# panel7.net
KiCad netlist of a schematic drawn in Altium Designer
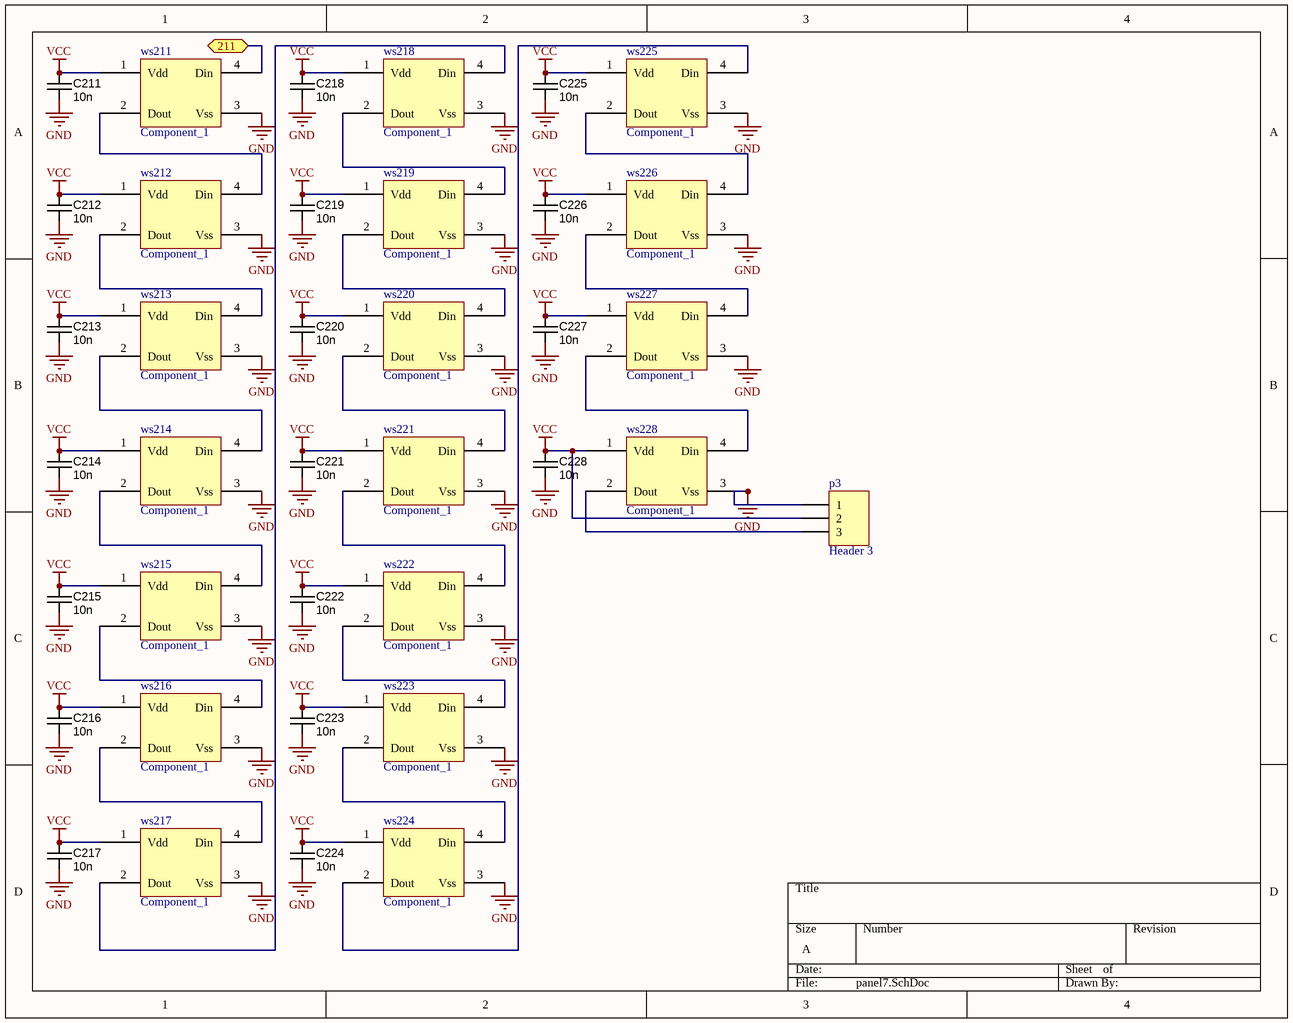
[diagram p0: panel7.SchDoc]

(export (version "E")
  (design (tool "Eeschema 10.0.6"))
  (components
    (comp (ref "C211")
      (value "10n")
      (footprint "CAPC1608X90N")
      (description "Capacitor SMD Cer 10nF 10% 100V X7R 0603")
      (fields
        (field (name "TOLERANCE") "±10%")
        (field (name "MANUFACTURER") "Murata Electronics North America")
      )
      (libsource (lib "PBL - Capacitors") (part "CAPC_10n_0603_X7R_100V_10%"))
    )
    (comp (ref "C212")
      (value "10n")
      (footprint "CAPC1608X90N")
      (description "Capacitor SMD Cer 10nF 10% 100V X7R 0603")
      (fields
        (field (name "TOLERANCE") "±10%")
        (field (name "MANUFACTURER") "Murata Electronics North America")
      )
      (libsource (lib "PBL - Capacitors") (part "CAPC_10n_0603_X7R_100V_10%"))
    )
    (comp (ref "C213")
      (value "10n")
      (footprint "CAPC1608X90N")
      (description "Capacitor SMD Cer 10nF 10% 100V X7R 0603")
      (fields
        (field (name "TOLERANCE") "±10%")
        (field (name "MANUFACTURER") "Murata Electronics North America")
      )
      (libsource (lib "PBL - Capacitors") (part "CAPC_10n_0603_X7R_100V_10%"))
    )
    (comp (ref "C214")
      (value "10n")
      (footprint "CAPC1608X90N")
      (description "Capacitor SMD Cer 10nF 10% 100V X7R 0603")
      (fields
        (field (name "TOLERANCE") "±10%")
        (field (name "MANUFACTURER") "Murata Electronics North America")
      )
      (libsource (lib "PBL - Capacitors") (part "CAPC_10n_0603_X7R_100V_10%"))
    )
    (comp (ref "C215")
      (value "10n")
      (footprint "CAPC1608X90N")
      (description "Capacitor SMD Cer 10nF 10% 100V X7R 0603")
      (fields
        (field (name "TOLERANCE") "±10%")
        (field (name "MANUFACTURER") "Murata Electronics North America")
      )
      (libsource (lib "PBL - Capacitors") (part "CAPC_10n_0603_X7R_100V_10%"))
    )
    (comp (ref "C216")
      (value "10n")
      (footprint "CAPC1608X90N")
      (description "Capacitor SMD Cer 10nF 10% 100V X7R 0603")
      (fields
        (field (name "TOLERANCE") "±10%")
        (field (name "MANUFACTURER") "Murata Electronics North America")
      )
      (libsource (lib "PBL - Capacitors") (part "CAPC_10n_0603_X7R_100V_10%"))
    )
    (comp (ref "C217")
      (value "10n")
      (footprint "CAPC1608X90N")
      (description "Capacitor SMD Cer 10nF 10% 100V X7R 0603")
      (fields
        (field (name "TOLERANCE") "±10%")
        (field (name "MANUFACTURER") "Murata Electronics North America")
      )
      (libsource (lib "PBL - Capacitors") (part "CAPC_10n_0603_X7R_100V_10%"))
    )
    (comp (ref "C218")
      (value "10n")
      (footprint "CAPC1608X90N")
      (description "Capacitor SMD Cer 10nF 10% 100V X7R 0603")
      (fields
        (field (name "TOLERANCE") "±10%")
        (field (name "MANUFACTURER") "Murata Electronics North America")
      )
      (libsource (lib "PBL - Capacitors") (part "CAPC_10n_0603_X7R_100V_10%"))
    )
    (comp (ref "C219")
      (value "10n")
      (footprint "CAPC1608X90N")
      (description "Capacitor SMD Cer 10nF 10% 100V X7R 0603")
      (fields
        (field (name "TOLERANCE") "±10%")
        (field (name "MANUFACTURER") "Murata Electronics North America")
      )
      (libsource (lib "PBL - Capacitors") (part "CAPC_10n_0603_X7R_100V_10%"))
    )
    (comp (ref "C220")
      (value "10n")
      (footprint "CAPC1608X90N")
      (description "Capacitor SMD Cer 10nF 10% 100V X7R 0603")
      (fields
        (field (name "TOLERANCE") "±10%")
        (field (name "MANUFACTURER") "Murata Electronics North America")
      )
      (libsource (lib "PBL - Capacitors") (part "CAPC_10n_0603_X7R_100V_10%"))
    )
    (comp (ref "C221")
      (value "10n")
      (footprint "CAPC1608X90N")
      (description "Capacitor SMD Cer 10nF 10% 100V X7R 0603")
      (fields
        (field (name "TOLERANCE") "±10%")
        (field (name "MANUFACTURER") "Murata Electronics North America")
      )
      (libsource (lib "PBL - Capacitors") (part "CAPC_10n_0603_X7R_100V_10%"))
    )
    (comp (ref "C222")
      (value "10n")
      (footprint "CAPC1608X90N")
      (description "Capacitor SMD Cer 10nF 10% 100V X7R 0603")
      (fields
        (field (name "TOLERANCE") "±10%")
        (field (name "MANUFACTURER") "Murata Electronics North America")
      )
      (libsource (lib "PBL - Capacitors") (part "CAPC_10n_0603_X7R_100V_10%"))
    )
    (comp (ref "C223")
      (value "10n")
      (footprint "CAPC1608X90N")
      (description "Capacitor SMD Cer 10nF 10% 100V X7R 0603")
      (fields
        (field (name "TOLERANCE") "±10%")
        (field (name "MANUFACTURER") "Murata Electronics North America")
      )
      (libsource (lib "PBL - Capacitors") (part "CAPC_10n_0603_X7R_100V_10%"))
    )
    (comp (ref "C224")
      (value "10n")
      (footprint "CAPC1608X90N")
      (description "Capacitor SMD Cer 10nF 10% 100V X7R 0603")
      (fields
        (field (name "TOLERANCE") "±10%")
        (field (name "MANUFACTURER") "Murata Electronics North America")
      )
      (libsource (lib "PBL - Capacitors") (part "CAPC_10n_0603_X7R_100V_10%"))
    )
    (comp (ref "C225")
      (value "10n")
      (footprint "CAPC1608X90N")
      (description "Capacitor SMD Cer 10nF 10% 100V X7R 0603")
      (fields
        (field (name "TOLERANCE") "±10%")
        (field (name "MANUFACTURER") "Murata Electronics North America")
      )
      (libsource (lib "PBL - Capacitors") (part "CAPC_10n_0603_X7R_100V_10%"))
    )
    (comp (ref "C226")
      (value "10n")
      (footprint "CAPC1608X90N")
      (description "Capacitor SMD Cer 10nF 10% 100V X7R 0603")
      (fields
        (field (name "TOLERANCE") "±10%")
        (field (name "MANUFACTURER") "Murata Electronics North America")
      )
      (libsource (lib "PBL - Capacitors") (part "CAPC_10n_0603_X7R_100V_10%"))
    )
    (comp (ref "C227")
      (value "10n")
      (footprint "CAPC1608X90N")
      (description "Capacitor SMD Cer 10nF 10% 100V X7R 0603")
      (fields
        (field (name "TOLERANCE") "±10%")
        (field (name "MANUFACTURER") "Murata Electronics North America")
      )
      (libsource (lib "PBL - Capacitors") (part "CAPC_10n_0603_X7R_100V_10%"))
    )
    (comp (ref "C228")
      (value "10n")
      (footprint "CAPC1608X90N")
      (description "Capacitor SMD Cer 10nF 10% 100V X7R 0603")
      (fields
        (field (name "TOLERANCE") "±10%")
        (field (name "MANUFACTURER") "Murata Electronics North America")
      )
      (libsource (lib "PBL - Capacitors") (part "CAPC_10n_0603_X7R_100V_10%"))
    )
    (comp (ref "p3")
      (value "Header 3")
      (footprint "HDR1X3")
      (description "Header, 3-Pin")
      (fields (field (name "PUBLISHER") "Altium Limited"))
      (libsource (lib "Miscellaneous Connectors") (part "Header 3"))
    )
    (comp (ref "ws211")
      (value "Component_1")
      (footprint "SOP4")
      (libsource (lib "ws2812b") (part "Component_1"))
    )
    (comp (ref "ws212")
      (value "Component_1")
      (footprint "SOP4")
      (libsource (lib "ws2812b") (part "Component_1"))
    )
    (comp (ref "ws213")
      (value "Component_1")
      (footprint "SOP4")
      (libsource (lib "ws2812b") (part "Component_1"))
    )
    (comp (ref "ws214")
      (value "Component_1")
      (footprint "SOP4")
      (libsource (lib "ws2812b") (part "Component_1"))
    )
    (comp (ref "ws215")
      (value "Component_1")
      (footprint "SOP4")
      (libsource (lib "ws2812b") (part "Component_1"))
    )
    (comp (ref "ws216")
      (value "Component_1")
      (footprint "SOP4")
      (libsource (lib "ws2812b") (part "Component_1"))
    )
    (comp (ref "ws217")
      (value "Component_1")
      (footprint "SOP4")
      (libsource (lib "ws2812b") (part "Component_1"))
    )
    (comp (ref "ws218")
      (value "Component_1")
      (footprint "SOP4")
      (libsource (lib "ws2812b") (part "Component_1"))
    )
    (comp (ref "ws219")
      (value "Component_1")
      (footprint "SOP4")
      (libsource (lib "ws2812b") (part "Component_1"))
    )
    (comp (ref "ws220")
      (value "Component_1")
      (footprint "SOP4")
      (libsource (lib "ws2812b") (part "Component_1"))
    )
    (comp (ref "ws221")
      (value "Component_1")
      (footprint "SOP4")
      (libsource (lib "ws2812b") (part "Component_1"))
    )
    (comp (ref "ws222")
      (value "Component_1")
      (footprint "SOP4")
      (libsource (lib "ws2812b") (part "Component_1"))
    )
    (comp (ref "ws223")
      (value "Component_1")
      (footprint "SOP4")
      (libsource (lib "ws2812b") (part "Component_1"))
    )
    (comp (ref "ws224")
      (value "Component_1")
      (footprint "SOP4")
      (libsource (lib "ws2812b") (part "Component_1"))
    )
    (comp (ref "ws225")
      (value "Component_1")
      (footprint "SOP4")
      (libsource (lib "ws2812b") (part "Component_1"))
    )
    (comp (ref "ws226")
      (value "Component_1")
      (footprint "SOP4")
      (libsource (lib "ws2812b") (part "Component_1"))
    )
    (comp (ref "ws227")
      (value "Component_1")
      (footprint "SOP4")
      (libsource (lib "ws2812b") (part "Component_1"))
    )
    (comp (ref "ws228")
      (value "Component_1")
      (footprint "SOP4")
      (libsource (lib "ws2812b") (part "Component_1"))
    )
  )
  (nets
    (net (code "1") (name "/211") (class "Default")
      (node (ref "ws211") (pin "4") (pinfunction "Din_4") (pintype "passive"))
    )
    (net (code "2") (name "GND") (class "Default")
      (node (ref "C211") (pin "2") (pintype "passive"))
      (node (ref "C212") (pin "2") (pintype "passive"))
      (node (ref "C213") (pin "2") (pintype "passive"))
      (node (ref "C214") (pin "2") (pintype "passive"))
      (node (ref "C215") (pin "2") (pintype "passive"))
      (node (ref "C216") (pin "2") (pintype "passive"))
      (node (ref "C217") (pin "2") (pintype "passive"))
      (node (ref "C218") (pin "2") (pintype "passive"))
      (node (ref "C219") (pin "2") (pintype "passive"))
      (node (ref "C220") (pin "2") (pintype "passive"))
      (node (ref "C221") (pin "2") (pintype "passive"))
      (node (ref "C222") (pin "2") (pintype "passive"))
      (node (ref "C223") (pin "2") (pintype "passive"))
      (node (ref "C224") (pin "2") (pintype "passive"))
      (node (ref "C225") (pin "2") (pintype "passive"))
      (node (ref "C226") (pin "2") (pintype "passive"))
      (node (ref "C227") (pin "2") (pintype "passive"))
      (node (ref "C228") (pin "2") (pintype "passive"))
      (node (ref "p3") (pin "1") (pinfunction "1_1") (pintype "passive"))
      (node (ref "ws211") (pin "3") (pinfunction "Vss_3") (pintype "passive"))
      (node (ref "ws212") (pin "3") (pinfunction "Vss_3") (pintype "passive"))
      (node (ref "ws213") (pin "3") (pinfunction "Vss_3") (pintype "passive"))
      (node (ref "ws214") (pin "3") (pinfunction "Vss_3") (pintype "passive"))
      (node (ref "ws215") (pin "3") (pinfunction "Vss_3") (pintype "passive"))
      (node (ref "ws216") (pin "3") (pinfunction "Vss_3") (pintype "passive"))
      (node (ref "ws217") (pin "3") (pinfunction "Vss_3") (pintype "passive"))
      (node (ref "ws218") (pin "3") (pinfunction "Vss_3") (pintype "passive"))
      (node (ref "ws219") (pin "3") (pinfunction "Vss_3") (pintype "passive"))
      (node (ref "ws220") (pin "3") (pinfunction "Vss_3") (pintype "passive"))
      (node (ref "ws221") (pin "3") (pinfunction "Vss_3") (pintype "passive"))
      (node (ref "ws222") (pin "3") (pinfunction "Vss_3") (pintype "passive"))
      (node (ref "ws223") (pin "3") (pinfunction "Vss_3") (pintype "passive"))
      (node (ref "ws224") (pin "3") (pinfunction "Vss_3") (pintype "passive"))
      (node (ref "ws225") (pin "3") (pinfunction "Vss_3") (pintype "passive"))
      (node (ref "ws226") (pin "3") (pinfunction "Vss_3") (pintype "passive"))
      (node (ref "ws227") (pin "3") (pinfunction "Vss_3") (pintype "passive"))
      (node (ref "ws228") (pin "3") (pinfunction "Vss_3") (pintype "passive"))
    )
    (net (code "3") (name "Net-(ws211-Dout)") (class "Default")
      (node (ref "ws211") (pin "2") (pinfunction "Dout_2") (pintype "passive"))
      (node (ref "ws212") (pin "4") (pinfunction "Din_4") (pintype "passive"))
    )
    (net (code "4") (name "Net-(ws212-Dout)") (class "Default")
      (node (ref "ws212") (pin "2") (pinfunction "Dout_2") (pintype "passive"))
      (node (ref "ws213") (pin "4") (pinfunction "Din_4") (pintype "passive"))
    )
    (net (code "5") (name "Net-(ws213-Dout)") (class "Default")
      (node (ref "ws213") (pin "2") (pinfunction "Dout_2") (pintype "passive"))
      (node (ref "ws214") (pin "4") (pinfunction "Din_4") (pintype "passive"))
    )
    (net (code "6") (name "Net-(ws214-Dout)") (class "Default")
      (node (ref "ws214") (pin "2") (pinfunction "Dout_2") (pintype "passive"))
      (node (ref "ws215") (pin "4") (pinfunction "Din_4") (pintype "passive"))
    )
    (net (code "7") (name "Net-(ws215-Dout)") (class "Default")
      (node (ref "ws215") (pin "2") (pinfunction "Dout_2") (pintype "passive"))
      (node (ref "ws216") (pin "4") (pinfunction "Din_4") (pintype "passive"))
    )
    (net (code "8") (name "Net-(ws216-Dout)") (class "Default")
      (node (ref "ws216") (pin "2") (pinfunction "Dout_2") (pintype "passive"))
      (node (ref "ws217") (pin "4") (pinfunction "Din_4") (pintype "passive"))
    )
    (net (code "9") (name "Net-(ws217-Dout)") (class "Default")
      (node (ref "ws217") (pin "2") (pinfunction "Dout_2") (pintype "passive"))
      (node (ref "ws218") (pin "4") (pinfunction "Din_4") (pintype "passive"))
    )
    (net (code "10") (name "Net-(ws218-Dout)") (class "Default")
      (node (ref "ws218") (pin "2") (pinfunction "Dout_2") (pintype "passive"))
      (node (ref "ws219") (pin "4") (pinfunction "Din_4") (pintype "passive"))
    )
    (net (code "11") (name "Net-(ws219-Dout)") (class "Default")
      (node (ref "ws219") (pin "2") (pinfunction "Dout_2") (pintype "passive"))
      (node (ref "ws220") (pin "4") (pinfunction "Din_4") (pintype "passive"))
    )
    (net (code "12") (name "Net-(ws220-Dout)") (class "Default")
      (node (ref "ws220") (pin "2") (pinfunction "Dout_2") (pintype "passive"))
      (node (ref "ws221") (pin "4") (pinfunction "Din_4") (pintype "passive"))
    )
    (net (code "13") (name "Net-(ws221-Dout)") (class "Default")
      (node (ref "ws221") (pin "2") (pinfunction "Dout_2") (pintype "passive"))
      (node (ref "ws222") (pin "4") (pinfunction "Din_4") (pintype "passive"))
    )
    (net (code "14") (name "Net-(ws222-Dout)") (class "Default")
      (node (ref "ws222") (pin "2") (pinfunction "Dout_2") (pintype "passive"))
      (node (ref "ws223") (pin "4") (pinfunction "Din_4") (pintype "passive"))
    )
    (net (code "15") (name "Net-(ws223-Dout)") (class "Default")
      (node (ref "ws223") (pin "2") (pinfunction "Dout_2") (pintype "passive"))
      (node (ref "ws224") (pin "4") (pinfunction "Din_4") (pintype "passive"))
    )
    (net (code "16") (name "Net-(ws224-Dout)") (class "Default")
      (node (ref "ws224") (pin "2") (pinfunction "Dout_2") (pintype "passive"))
      (node (ref "ws225") (pin "4") (pinfunction "Din_4") (pintype "passive"))
    )
    (net (code "17") (name "Net-(ws225-Dout)") (class "Default")
      (node (ref "ws225") (pin "2") (pinfunction "Dout_2") (pintype "passive"))
      (node (ref "ws226") (pin "4") (pinfunction "Din_4") (pintype "passive"))
    )
    (net (code "18") (name "Net-(ws226-Dout)") (class "Default")
      (node (ref "ws226") (pin "2") (pinfunction "Dout_2") (pintype "passive"))
      (node (ref "ws227") (pin "4") (pinfunction "Din_4") (pintype "passive"))
    )
    (net (code "19") (name "Net-(ws227-Dout)") (class "Default")
      (node (ref "ws227") (pin "2") (pinfunction "Dout_2") (pintype "passive"))
      (node (ref "ws228") (pin "4") (pinfunction "Din_4") (pintype "passive"))
    )
    (net (code "20") (name "Net-(ws228-Dout)") (class "Default")
      (node (ref "p3") (pin "3") (pinfunction "3_3") (pintype "passive"))
      (node (ref "ws228") (pin "2") (pinfunction "Dout_2") (pintype "passive"))
    )
    (net (code "21") (name "VCC") (class "Default")
      (node (ref "C211") (pin "1") (pintype "passive"))
      (node (ref "C212") (pin "1") (pintype "passive"))
      (node (ref "C213") (pin "1") (pintype "passive"))
      (node (ref "C214") (pin "1") (pintype "passive"))
      (node (ref "C215") (pin "1") (pintype "passive"))
      (node (ref "C216") (pin "1") (pintype "passive"))
      (node (ref "C217") (pin "1") (pintype "passive"))
      (node (ref "C218") (pin "1") (pintype "passive"))
      (node (ref "C219") (pin "1") (pintype "passive"))
      (node (ref "C220") (pin "1") (pintype "passive"))
      (node (ref "C221") (pin "1") (pintype "passive"))
      (node (ref "C222") (pin "1") (pintype "passive"))
      (node (ref "C223") (pin "1") (pintype "passive"))
      (node (ref "C224") (pin "1") (pintype "passive"))
      (node (ref "C225") (pin "1") (pintype "passive"))
      (node (ref "C226") (pin "1") (pintype "passive"))
      (node (ref "C227") (pin "1") (pintype "passive"))
      (node (ref "C228") (pin "1") (pintype "passive"))
      (node (ref "p3") (pin "2") (pinfunction "2_2") (pintype "passive"))
      (node (ref "ws211") (pin "1") (pinfunction "Vdd_1") (pintype "passive"))
      (node (ref "ws212") (pin "1") (pinfunction "Vdd_1") (pintype "passive"))
      (node (ref "ws213") (pin "1") (pinfunction "Vdd_1") (pintype "passive"))
      (node (ref "ws214") (pin "1") (pinfunction "Vdd_1") (pintype "passive"))
      (node (ref "ws215") (pin "1") (pinfunction "Vdd_1") (pintype "passive"))
      (node (ref "ws216") (pin "1") (pinfunction "Vdd_1") (pintype "passive"))
      (node (ref "ws217") (pin "1") (pinfunction "Vdd_1") (pintype "passive"))
      (node (ref "ws218") (pin "1") (pinfunction "Vdd_1") (pintype "passive"))
      (node (ref "ws219") (pin "1") (pinfunction "Vdd_1") (pintype "passive"))
      (node (ref "ws220") (pin "1") (pinfunction "Vdd_1") (pintype "passive"))
      (node (ref "ws221") (pin "1") (pinfunction "Vdd_1") (pintype "passive"))
      (node (ref "ws222") (pin "1") (pinfunction "Vdd_1") (pintype "passive"))
      (node (ref "ws223") (pin "1") (pinfunction "Vdd_1") (pintype "passive"))
      (node (ref "ws224") (pin "1") (pinfunction "Vdd_1") (pintype "passive"))
      (node (ref "ws225") (pin "1") (pinfunction "Vdd_1") (pintype "passive"))
      (node (ref "ws226") (pin "1") (pinfunction "Vdd_1") (pintype "passive"))
      (node (ref "ws227") (pin "1") (pinfunction "Vdd_1") (pintype "passive"))
      (node (ref "ws228") (pin "1") (pinfunction "Vdd_1") (pintype "passive"))
    )
  )
)
